# pcb_serial-adapter_serial-adapter.net
KiCad netlist of a schematic drawn in EAGLE
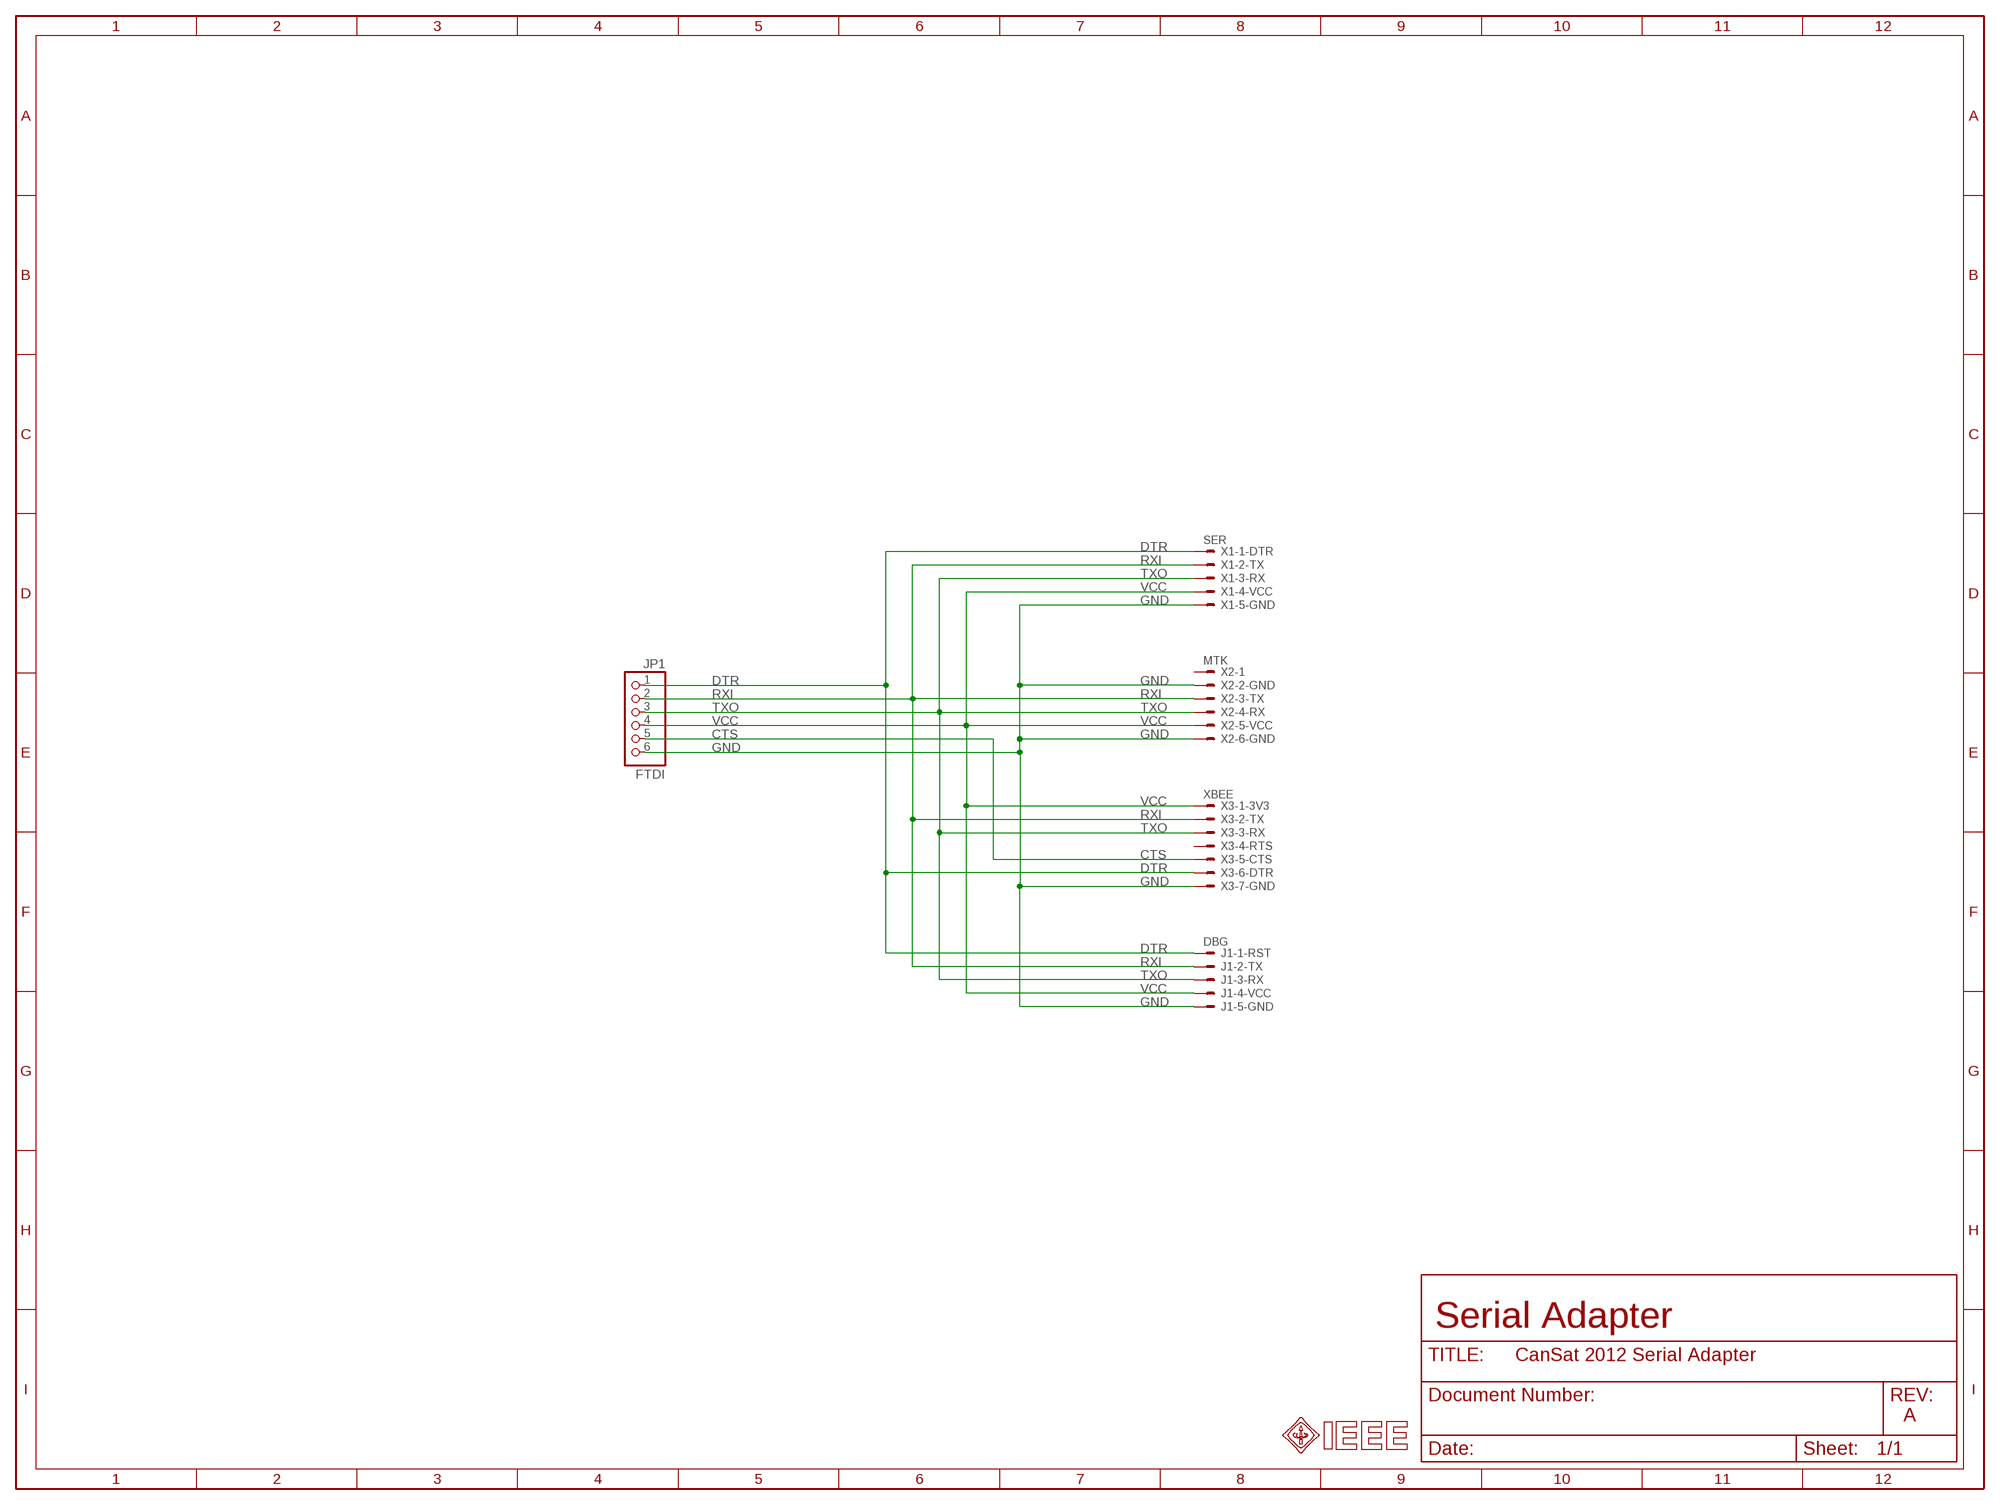
[diagram p0: schematic, sheet 1]

(export (version "E")
  (design (tool "Eeschema 10.0.6"))
  (components
    (comp (ref "J1")
      (value "DBG")
      (footprint "eagle-import:S5B-PH-SM4-TB")
      (libsource (lib "eagle-import") (part "JST-PH-5-DBG-STB"))
    )
    (comp (ref "JP1")
      (value "FTDI")
      (footprint "eagle-import:1X06")
      (libsource (lib "eagle-import") (part "PINHD-1X6"))
    )
    (comp (ref "X1")
      (value "SER")
      (footprint "eagle-import:SM05B-SRSS-TB")
      (libsource (lib "eagle-import") (part "?M05B-SRSS-TB-SERS"))
    )
    (comp (ref "X2")
      (value "MTK")
      (footprint "eagle-import:SM06B-SRSS-TB")
      (libsource (lib "eagle-import") (part "?M06B-SRSS-TB-MTKS"))
    )
    (comp (ref "X3")
      (value "XBEE")
      (footprint "eagle-import:SM07B-SRSS-TB")
      (libsource (lib "eagle-import") (part "?M07B-SRSS-TB-XBEES"))
    )
  )
  (nets
    (net (code "1") (name "/CTS") (class "Default")
      (node (ref "JP1") (pin "5") (pinfunction "5_5") (pintype "passive"))
      (node (ref "X3") (pin "5") (pinfunction "S_5") (pintype "passive"))
    )
    (net (code "2") (name "/DTR") (class "Default")
      (node (ref "J1") (pin "1") (pinfunction "S_1") (pintype "passive"))
      (node (ref "JP1") (pin "1") (pinfunction "1_1") (pintype "passive"))
      (node (ref "X1") (pin "1") (pinfunction "S_1") (pintype "passive"))
      (node (ref "X3") (pin "6") (pinfunction "S_6") (pintype "passive"))
    )
    (net (code "3") (name "/GND") (class "Default")
      (node (ref "J1") (pin "5") (pinfunction "S_5") (pintype "passive"))
      (node (ref "JP1") (pin "6") (pinfunction "6_6") (pintype "passive"))
      (node (ref "X1") (pin "5") (pinfunction "S_5") (pintype "passive"))
      (node (ref "X2") (pin "2") (pinfunction "S_2") (pintype "passive"))
      (node (ref "X2") (pin "6") (pinfunction "S_6") (pintype "passive"))
      (node (ref "X3") (pin "7") (pinfunction "S_7") (pintype "passive"))
    )
    (net (code "4") (name "/RXI") (class "Default")
      (node (ref "J1") (pin "2") (pinfunction "S_2") (pintype "passive"))
      (node (ref "JP1") (pin "2") (pinfunction "2_2") (pintype "passive"))
      (node (ref "X1") (pin "2") (pinfunction "S_2") (pintype "passive"))
      (node (ref "X2") (pin "3") (pinfunction "S_3") (pintype "passive"))
      (node (ref "X3") (pin "2") (pinfunction "S_2") (pintype "passive"))
    )
    (net (code "5") (name "/TXO") (class "Default")
      (node (ref "J1") (pin "3") (pinfunction "S_3") (pintype "passive"))
      (node (ref "JP1") (pin "3") (pinfunction "3_3") (pintype "passive"))
      (node (ref "X1") (pin "3") (pinfunction "S_3") (pintype "passive"))
      (node (ref "X2") (pin "4") (pinfunction "S_4") (pintype "passive"))
      (node (ref "X3") (pin "3") (pinfunction "S_3") (pintype "passive"))
    )
    (net (code "6") (name "/VCC") (class "Default")
      (node (ref "J1") (pin "4") (pinfunction "S_4") (pintype "passive"))
      (node (ref "JP1") (pin "4") (pinfunction "4_4") (pintype "passive"))
      (node (ref "X1") (pin "4") (pinfunction "S_4") (pintype "passive"))
      (node (ref "X2") (pin "5") (pinfunction "S_5") (pintype "passive"))
      (node (ref "X3") (pin "1") (pinfunction "S_1") (pintype "passive"))
    )
    (net (code "7") (name "unconnected-(X2A-S-Pad1)") (class "Default")
      (node (ref "X2") (pin "1") (pinfunction "S_1") (pintype "passive"))
    )
    (net (code "8") (name "unconnected-(X3D-S-Pad4)") (class "Default")
      (node (ref "X3") (pin "4") (pinfunction "S_4") (pintype "passive"))
    )
  )
)
